# LIS3MDL_LSM6DS3_rev_A.net
KiCad netlist of a schematic drawn in EAGLE
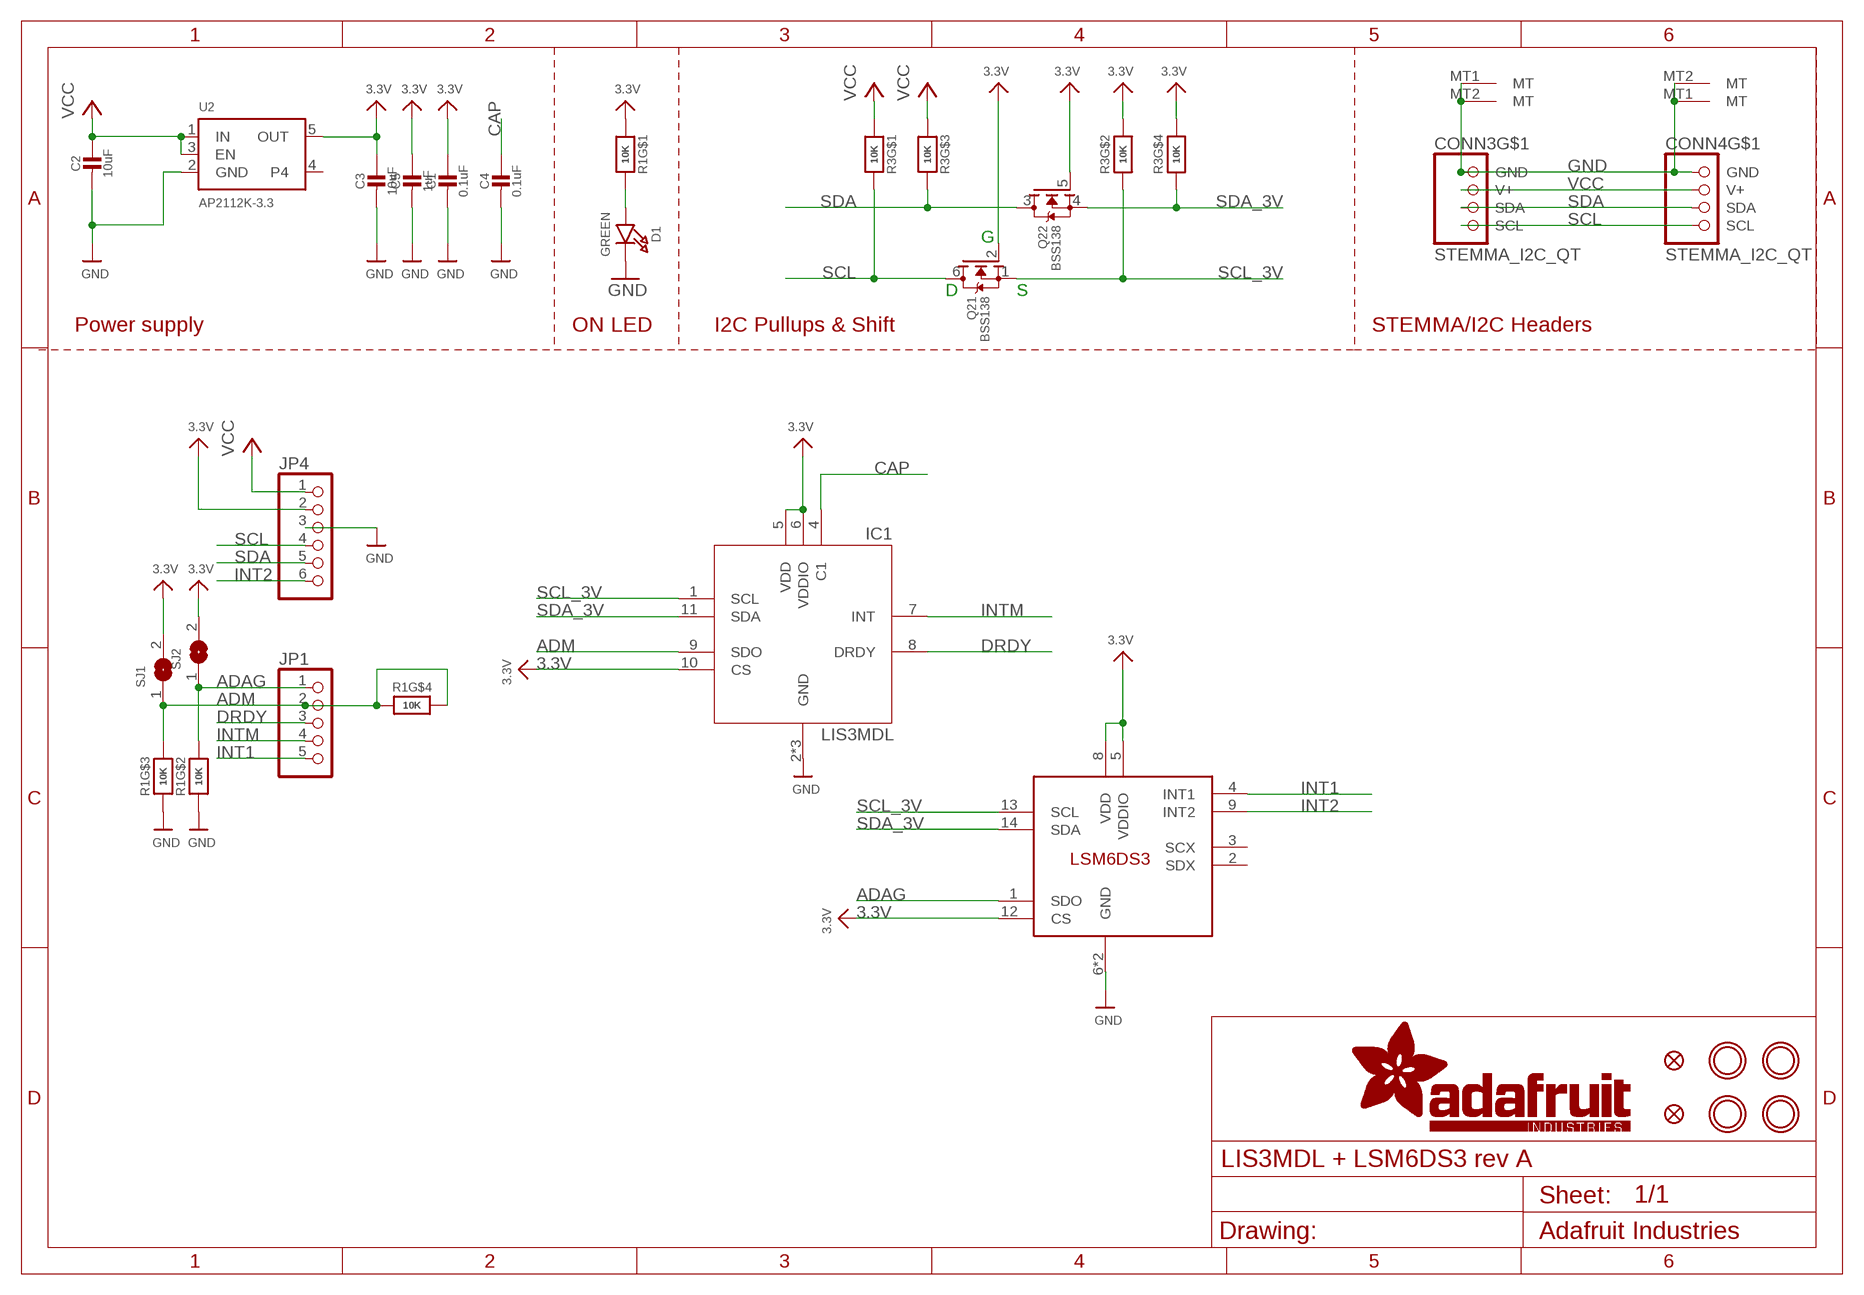
[diagram p0: schematic, sheet 1]

(export (version "E")
  (design (tool "Eeschema 10.0.6"))
  (components
    (comp (ref "C1")
      (value "0.1uF")
      (footprint "eagle-import:0603-NO")
      (libsource (lib "eagle-import") (part "CAP_CERAMIC0603_NO"))
    )
    (comp (ref "C2")
      (value "10uF")
      (footprint "eagle-import:0805-NO")
      (libsource (lib "eagle-import") (part "CAP_CERAMIC0805-NOOUTLINE"))
    )
    (comp (ref "C3")
      (value "10uF")
      (footprint "eagle-import:0805-NO")
      (libsource (lib "eagle-import") (part "CAP_CERAMIC0805-NOOUTLINE"))
    )
    (comp (ref "C4")
      (value "0.1uF")
      (footprint "eagle-import:0603-NO")
      (libsource (lib "eagle-import") (part "CAP_CERAMIC0603_NO"))
    )
    (comp (ref "C5")
      (value "1uF")
      (footprint "eagle-import:0603-NO")
      (libsource (lib "eagle-import") (part "CAP_CERAMIC0603_NO"))
    )
    (comp (ref "CONN3")
      (value "STEMMA_I2C_QT")
      (footprint "eagle-import:JST_SH4")
      (libsource (lib "eagle-import") (part "STEMMA_I2C_QT"))
    )
    (comp (ref "CONN4")
      (value "STEMMA_I2C_QT")
      (footprint "eagle-import:JST_SH4")
      (libsource (lib "eagle-import") (part "STEMMA_I2C_QT"))
    )
    (comp (ref "D1")
      (value "GREEN")
      (footprint "eagle-import:CHIPLED_0603_NOOUTLINE")
      (libsource (lib "eagle-import") (part "LED0603_NOOUTLINE"))
    )
    (comp (ref "FID3")
      (value "FIDUCIAL_1MM")
      (footprint "eagle-import:FIDUCIAL_1MM")
      (libsource (lib "eagle-import") (part "FIDUCIAL_1MM"))
    )
    (comp (ref "FID4")
      (value "FIDUCIAL_1MM")
      (footprint "eagle-import:FIDUCIAL_1MM")
      (libsource (lib "eagle-import") (part "FIDUCIAL_1MM"))
    )
    (comp (ref "IC1")
      (value "LIS3MDL")
      (footprint "eagle-import:LGA12_2X2MM")
      (libsource (lib "eagle-import") (part "LIS3MDL"))
    )
    (comp (ref "JP1")
      (value "HEADER-1X570MIL")
      (footprint "eagle-import:1X05_ROUND_70")
      (libsource (lib "eagle-import") (part "HEADER-1X570MIL"))
    )
    (comp (ref "JP4")
      (value "HEADER-1X670MIL")
      (footprint "eagle-import:1X06_ROUND_70")
      (libsource (lib "eagle-import") (part "HEADER-1X670MIL"))
    )
    (comp (ref "Q2")
      (value "BSS138")
      (footprint "eagle-import:SOT363")
      (libsource (lib "eagle-import") (part "MOSFET-N_DUAL"))
    )
    (comp (ref "R1")
      (value "10K")
      (footprint "eagle-import:RESPACK_4X0603")
      (libsource (lib "eagle-import") (part "RESISTOR_4PACK"))
    )
    (comp (ref "R3")
      (value "10K")
      (footprint "eagle-import:RESPACK_4X0603")
      (libsource (lib "eagle-import") (part "RESISTOR_4PACK"))
    )
    (comp (ref "SJ1")
      (value "SOLDERJUMPER")
      (footprint "eagle-import:SOLDERJUMPER_ARROW_NOPASTE")
      (libsource (lib "eagle-import") (part "SOLDERJUMPER"))
    )
    (comp (ref "SJ2")
      (value "SOLDERJUMPER")
      (footprint "eagle-import:SOLDERJUMPER_ARROW_NOPASTE")
      (libsource (lib "eagle-import") (part "SOLDERJUMPER"))
    )
    (comp (ref "U$1")
      (value "MOUNTINGHOLE2.5")
      (footprint "eagle-import:MOUNTINGHOLE_2.5_PLATED")
      (libsource (lib "eagle-import") (part "MOUNTINGHOLE2.5"))
    )
    (comp (ref "U$17")
      (value "MOUNTINGHOLE2.5")
      (footprint "eagle-import:MOUNTINGHOLE_2.5_PLATED")
      (libsource (lib "eagle-import") (part "MOUNTINGHOLE2.5"))
    )
    (comp (ref "U$19")
      (value "MOUNTINGHOLE2.5")
      (footprint "eagle-import:MOUNTINGHOLE_2.5_PLATED")
      (libsource (lib "eagle-import") (part "MOUNTINGHOLE2.5"))
    )
    (comp (ref "U$21")
      (value "MOUNTINGHOLE2.5")
      (footprint "eagle-import:MOUNTINGHOLE_2.5_PLATED")
      (libsource (lib "eagle-import") (part "MOUNTINGHOLE2.5"))
    )
    (comp (ref "U$36")
      (value "LSM6DS3")
      (footprint "eagle-import:LGA-14L")
      (libsource (lib "eagle-import") (part "LSM6DS3"))
    )
    (comp (ref "U2")
      (value "AP2112K-3.3")
      (footprint "eagle-import:SOT23-5")
      (libsource (lib "eagle-import") (part "VREG_SOT23-5"))
    )
  )
  (nets
    (net (code "1") (name "/ADAG") (class "Default")
      (node (ref "JP1") (pin "1") (pinfunction "1_1") (pintype "passive"))
      (node (ref "R1") (pin "7") (pinfunction "2_7") (pintype "passive"))
      (node (ref "SJ2") (pin "1") (pinfunction "1_1") (pintype "passive"))
      (node (ref "U$36") (pin "1") (pinfunction "SDO_1") (pintype "bidirectional"))
    )
    (net (code "2") (name "/ADM") (class "Default")
      (node (ref "IC1") (pin "9") (pinfunction "SDO_9") (pintype "bidirectional"))
      (node (ref "JP1") (pin "2") (pinfunction "2_2") (pintype "passive"))
      (node (ref "R1") (pin "4") (pinfunction "1_4") (pintype "passive"))
      (node (ref "R1") (pin "5") (pinfunction "2_5") (pintype "passive"))
      (node (ref "R1") (pin "6") (pinfunction "2_6") (pintype "passive"))
      (node (ref "SJ1") (pin "1") (pinfunction "1_1") (pintype "passive"))
    )
    (net (code "3") (name "/CAP") (class "Default")
      (node (ref "C4") (pin "1") (pinfunction "1_1") (pintype "passive"))
      (node (ref "IC1") (pin "4") (pinfunction "C1_4") (pintype "input"))
    )
    (net (code "4") (name "/DRDY") (class "Default")
      (node (ref "IC1") (pin "8") (pinfunction "DRDY_8") (pintype "output"))
      (node (ref "JP1") (pin "3") (pinfunction "3_3") (pintype "passive"))
    )
    (net (code "5") (name "/INT1") (class "Default")
      (node (ref "JP1") (pin "5") (pinfunction "5_5") (pintype "passive"))
      (node (ref "U$36") (pin "4") (pinfunction "INT1_4") (pintype "bidirectional"))
    )
    (net (code "6") (name "/INT2") (class "Default")
      (node (ref "JP4") (pin "6") (pinfunction "6_6") (pintype "passive"))
      (node (ref "U$36") (pin "9") (pinfunction "INT2_9") (pintype "bidirectional"))
    )
    (net (code "7") (name "/INTM") (class "Default")
      (node (ref "IC1") (pin "7") (pinfunction "INT_7") (pintype "output"))
      (node (ref "JP1") (pin "4") (pinfunction "4_4") (pintype "passive"))
    )
    (net (code "8") (name "/SCL") (class "Default")
      (node (ref "CONN3") (pin "4") (pinfunction "SCL_4") (pintype "passive"))
      (node (ref "CONN4") (pin "4") (pinfunction "SCL_4") (pintype "passive"))
      (node (ref "JP4") (pin "4") (pinfunction "4_4") (pintype "passive"))
      (node (ref "Q2") (pin "6") (pinfunction "D_6") (pintype "bidirectional"))
      (node (ref "R3") (pin "8") (pinfunction "2_8") (pintype "passive"))
    )
    (net (code "9") (name "/SCL_3V") (class "Default")
      (node (ref "IC1") (pin "1") (pinfunction "SCL_1") (pintype "input"))
      (node (ref "Q2") (pin "1") (pinfunction "S_1") (pintype "bidirectional"))
      (node (ref "R3") (pin "7") (pinfunction "2_7") (pintype "passive"))
      (node (ref "U$36") (pin "13") (pinfunction "SCL_13") (pintype "bidirectional"))
    )
    (net (code "10") (name "/SDA") (class "Default")
      (node (ref "CONN3") (pin "3") (pinfunction "SDA_3") (pintype "passive"))
      (node (ref "CONN4") (pin "3") (pinfunction "SDA_3") (pintype "passive"))
      (node (ref "JP4") (pin "5") (pinfunction "5_5") (pintype "passive"))
      (node (ref "Q2") (pin "3") (pinfunction "D_3") (pintype "bidirectional"))
      (node (ref "R3") (pin "6") (pinfunction "2_6") (pintype "passive"))
    )
    (net (code "11") (name "/SDA_3V") (class "Default")
      (node (ref "IC1") (pin "11") (pinfunction "SDA_11") (pintype "bidirectional"))
      (node (ref "Q2") (pin "4") (pinfunction "S_4") (pintype "bidirectional"))
      (node (ref "R3") (pin "5") (pinfunction "2_5") (pintype "passive"))
      (node (ref "U$36") (pin "14") (pinfunction "SDA_14") (pintype "bidirectional"))
    )
    (net (code "12") (name "3.3V") (class "Default")
      (node (ref "C1") (pin "1") (pinfunction "1_1") (pintype "passive"))
      (node (ref "C3") (pin "1") (pinfunction "1_1") (pintype "passive"))
      (node (ref "C5") (pin "1") (pinfunction "1_1") (pintype "passive"))
      (node (ref "IC1") (pin "10") (pinfunction "CS_10") (pintype "input"))
      (node (ref "IC1") (pin "5") (pinfunction "VDD_5") (pintype "power_in"))
      (node (ref "IC1") (pin "6") (pinfunction "VDDIO_6") (pintype "power_in"))
      (node (ref "JP4") (pin "2") (pinfunction "2_2") (pintype "passive"))
      (node (ref "Q2") (pin "2") (pinfunction "G_2") (pintype "bidirectional"))
      (node (ref "Q2") (pin "5") (pinfunction "G_5") (pintype "bidirectional"))
      (node (ref "R1") (pin "1") (pinfunction "1_1") (pintype "passive"))
      (node (ref "R3") (pin "2") (pinfunction "1_2") (pintype "passive"))
      (node (ref "R3") (pin "4") (pinfunction "1_4") (pintype "passive"))
      (node (ref "SJ1") (pin "2") (pinfunction "2_2") (pintype "passive"))
      (node (ref "SJ2") (pin "2") (pinfunction "2_2") (pintype "passive"))
      (node (ref "U$36") (pin "12") (pinfunction "CS_12") (pintype "bidirectional"))
      (node (ref "U$36") (pin "5") (pinfunction "VDDIO_5") (pintype "power_in"))
      (node (ref "U$36") (pin "8") (pinfunction "VDD_8") (pintype "power_in"))
      (node (ref "U2") (pin "5") (pinfunction "OUT_5") (pintype "power_in"))
    )
    (net (code "13") (name "GND") (class "Default")
      (node (ref "C1") (pin "2") (pinfunction "2_2") (pintype "passive"))
      (node (ref "C2") (pin "2") (pinfunction "2_2") (pintype "passive"))
      (node (ref "C3") (pin "2") (pinfunction "2_2") (pintype "passive"))
      (node (ref "C4") (pin "2") (pinfunction "2_2") (pintype "passive"))
      (node (ref "C5") (pin "2") (pinfunction "2_2") (pintype "passive"))
      (node (ref "CONN3") (pin "1") (pinfunction "GND_1") (pintype "passive"))
      (node (ref "CONN3") (pin "MT1") (pinfunction "MT_MT1") (pintype "bidirectional"))
      (node (ref "CONN3") (pin "MT2") (pinfunction "MT_MT2") (pintype "bidirectional"))
      (node (ref "CONN4") (pin "1") (pinfunction "GND_1") (pintype "passive"))
      (node (ref "CONN4") (pin "MT1") (pinfunction "MT_MT1") (pintype "bidirectional"))
      (node (ref "CONN4") (pin "MT2") (pinfunction "MT_MT2") (pintype "bidirectional"))
      (node (ref "D1") (pin "C") (pinfunction "C_C") (pintype "passive"))
      (node (ref "IC1") (pin "12") (pinfunction "GND_12") (pintype "power_in"))
      (node (ref "IC1") (pin "2") (pinfunction "GND_2") (pintype "power_in"))
      (node (ref "IC1") (pin "3") (pinfunction "GND_3") (pintype "power_in"))
      (node (ref "JP4") (pin "3") (pinfunction "3_3") (pintype "passive"))
      (node (ref "R1") (pin "2") (pinfunction "1_2") (pintype "passive"))
      (node (ref "R1") (pin "3") (pinfunction "1_3") (pintype "passive"))
      (node (ref "U$36") (pin "6") (pinfunction "GND_6") (pintype "power_in"))
      (node (ref "U$36") (pin "7") (pinfunction "GND_7") (pintype "power_in"))
      (node (ref "U2") (pin "2") (pinfunction "GND_2") (pintype "power_in"))
    )
    (net (code "14") (name "Net-(R1A-2)") (class "Default")
      (node (ref "D1") (pin "A") (pinfunction "A_A") (pintype "passive"))
      (node (ref "R1") (pin "8") (pinfunction "2_8") (pintype "passive"))
    )
    (net (code "15") (name "VCC") (class "Default")
      (node (ref "C2") (pin "1") (pinfunction "1_1") (pintype "passive"))
      (node (ref "CONN3") (pin "2") (pinfunction "V+_2") (pintype "passive"))
      (node (ref "CONN4") (pin "2") (pinfunction "V+_2") (pintype "passive"))
      (node (ref "JP4") (pin "1") (pinfunction "1_1") (pintype "passive"))
      (node (ref "R3") (pin "1") (pinfunction "1_1") (pintype "passive"))
      (node (ref "R3") (pin "3") (pinfunction "1_3") (pintype "passive"))
      (node (ref "U2") (pin "1") (pinfunction "IN_1") (pintype "power_in"))
      (node (ref "U2") (pin "3") (pinfunction "EN_3") (pintype "input"))
    )
    (net (code "16") (name "unconnected-(U$36-SCX-Pad3)") (class "Default")
      (node (ref "U$36") (pin "3") (pinfunction "SCX_3") (pintype "bidirectional"))
    )
    (net (code "17") (name "unconnected-(U$36-SDX-Pad2)") (class "Default")
      (node (ref "U$36") (pin "2") (pinfunction "SDX_2") (pintype "bidirectional"))
    )
    (net (code "18") (name "unconnected-(U2-P4-Pad4)") (class "Default")
      (node (ref "U2") (pin "4") (pinfunction "P4_4") (pintype "bidirectional"))
    )
  )
)
